# Power_Supplies.net
KiCad netlist of a schematic drawn in Altium Designer
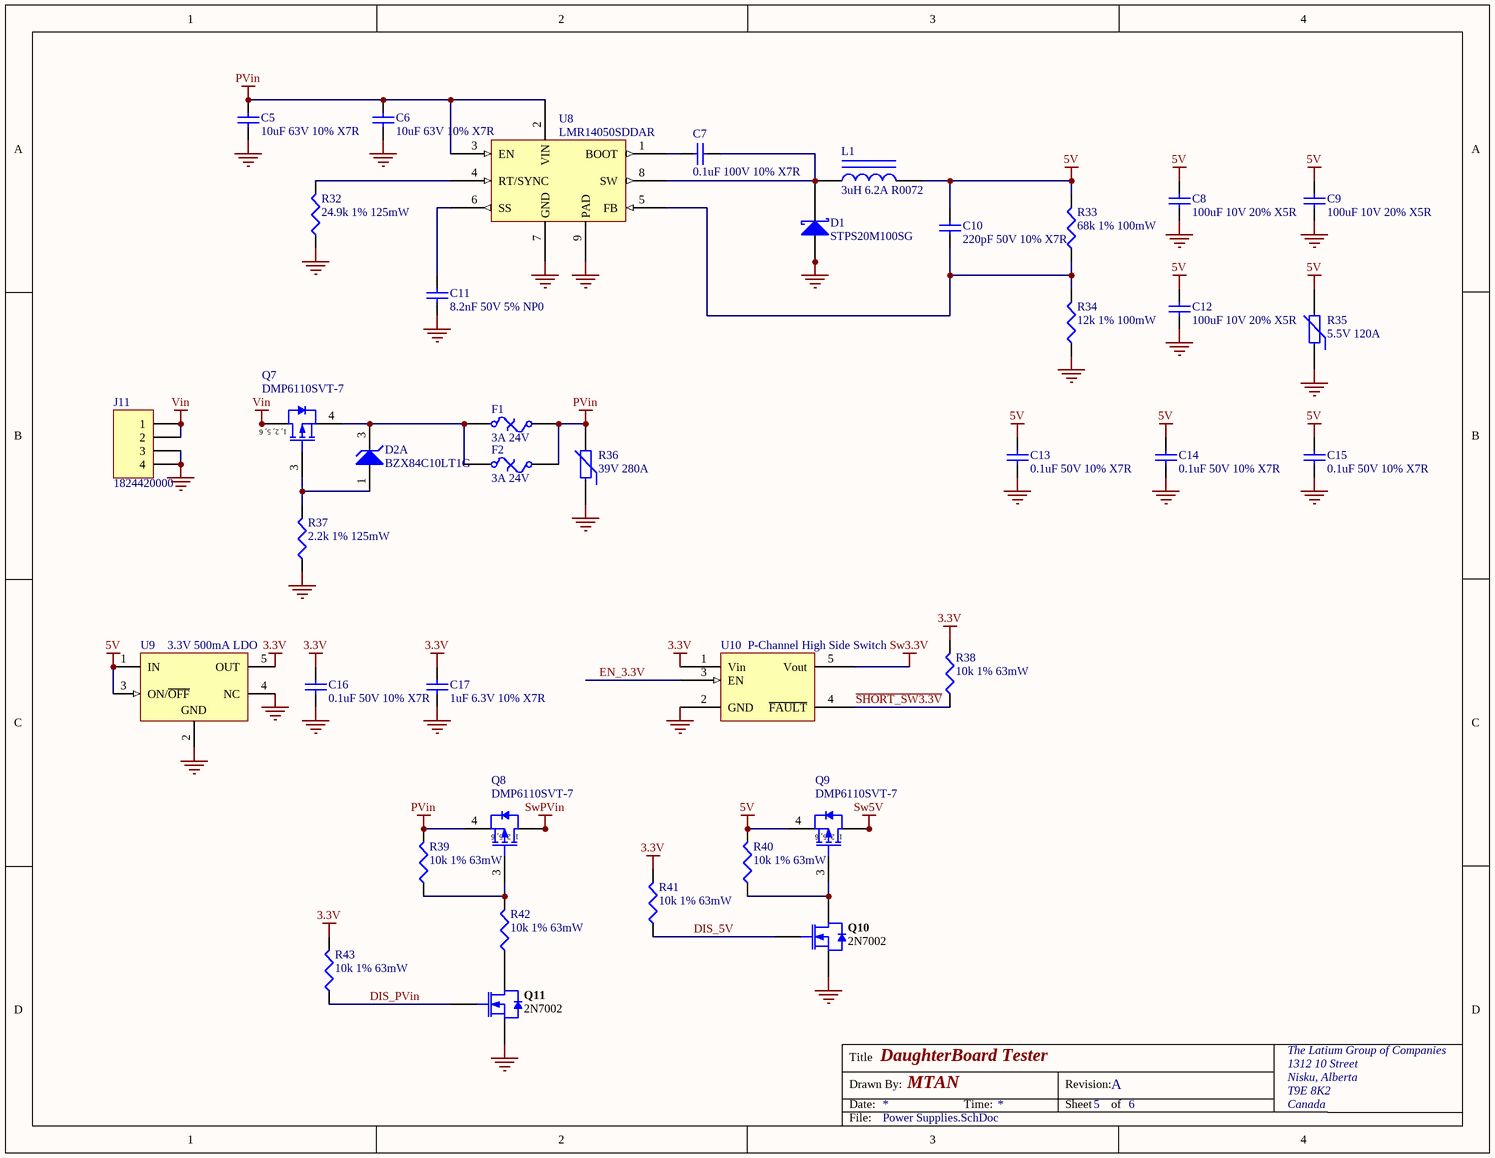
[diagram p0: Power Supplies.SchDoc]

(export (version "E")
  (design (tool "Eeschema 10.0.6"))
  (components
    (comp (ref "C5")
      (value "10uF 63V 10% X7R")
      (footprint "C1210_L")
      (description "Capacitor")
      (libsource (lib "Miscellaneous Devices") (part "Cap"))
    )
    (comp (ref "C6")
      (value "10uF 63V 10% X7R")
      (footprint "C1210_L")
      (description "Capacitor")
      (libsource (lib "Miscellaneous Devices") (part "Cap"))
    )
    (comp (ref "C7")
      (value "0.1uF 100V 10% X7R")
      (footprint "C0805")
      (description "Capacitor")
      (libsource (lib "Miscellaneous Devices") (part "Cap"))
    )
    (comp (ref "C8")
      (value "100uF 10V 20% X5R")
      (footprint "C1210_L")
      (description "Capacitor")
      (libsource (lib "Miscellaneous Devices") (part "Cap"))
    )
    (comp (ref "C9")
      (value "100uF 10V 20% X5R")
      (footprint "C1210_L")
      (description "Capacitor")
      (libsource (lib "Miscellaneous Devices") (part "Cap"))
    )
    (comp (ref "C10")
      (value "220pF 50V 10% X7R")
      (footprint "1608[0603]")
      (description "Capacitor")
      (libsource (lib "Miscellaneous Devices") (part "Cap"))
    )
    (comp (ref "C11")
      (value "8.2nF 50V 5% NP0")
      (footprint "1608[0603]")
      (description "Capacitor")
      (libsource (lib "Miscellaneous Devices") (part "Cap"))
    )
    (comp (ref "C12")
      (value "100uF 10V 20% X5R")
      (footprint "C1210_L")
      (description "Capacitor")
      (libsource (lib "Miscellaneous Devices") (part "Cap"))
    )
    (comp (ref "C13")
      (value "0.1uF 50V 10% X7R")
      (footprint "CAPC1005L")
      (description "Capacitor")
      (libsource (lib "Miscellaneous Devices") (part "Cap"))
    )
    (comp (ref "C14")
      (value "0.1uF 50V 10% X7R")
      (footprint "CAPC1005L")
      (description "Capacitor")
      (libsource (lib "Miscellaneous Devices") (part "Cap"))
    )
    (comp (ref "C15")
      (value "0.1uF 50V 10% X7R")
      (footprint "CAPC1005L")
      (description "Capacitor")
      (libsource (lib "Miscellaneous Devices") (part "Cap"))
    )
    (comp (ref "C16")
      (value "0.1uF 50V 10% X7R")
      (footprint "CAPC1005L")
      (description "Capacitor")
      (libsource (lib "Miscellaneous Devices") (part "Cap"))
    )
    (comp (ref "C17")
      (value "1uF 6.3V 10% X7R")
      (footprint "CAPC1005L")
      (description "Capacitor")
      (libsource (lib "Miscellaneous Devices") (part "Cap"))
    )
    (comp (ref "D1")
      (value "STPS20M100SG")
      (footprint "ONSC-D2PAK-3-418AJ_A_V")
      (description "DIODE SCHOTTKY 100V 20A D2PAK")
      (fields (field (name "MANUFACTURER") "STMicroelectronics"))
      (libsource (lib "Infineon Discrete Diode") (part "BAS70"))
    )
    (comp (ref "D2")
      (value "BZX84C10LT1G")
      (footprint "SOT23-3_L")
      (description "DIODE ZENER 10V 225MW SOT23-3")
      (fields (field (name "MANUFACTURER") "On Semiconductor"))
      (libsource (lib "ON Semi Zener Diodes") (part "BZX84C10LT1G"))
    )
    (comp (ref "F1")
      (value "3A 24V")
      (footprint "2920")
      (description "Thermal Fuse")
      (fields
        (field (name "MANUFACTURER PART NUMBER") "SMDC300F/24-2")
        (field (name "MANUFACTURER") "Littelfuse Inc")
      )
      (libsource (lib "Miscellaneous Devices") (part "Fuse Thermal"))
    )
    (comp (ref "F2")
      (value "3A 24V")
      (footprint "2920")
      (description "Thermal Fuse")
      (fields
        (field (name "MANUFACTURER PART NUMBER") "SMDC300F/24-2")
        (field (name "MANUFACTURER") "Littelfuse Inc")
      )
      (libsource (lib "Miscellaneous Devices") (part "Fuse Thermal"))
    )
    (comp (ref "J11")
      (value "1824420000")
      (footprint "1824420000")
      (description "TERM BLK 2POS SIDE ENT 3.5MM PCB")
      (fields (field (name "MANUFACTURER") "Weidmuller"))
      (libsource (lib "Miscellaneous Connectors") (part "Header 4H"))
    )
    (comp (ref "L1")
      (value "3uH 6.2A R0072")
      (footprint "SRU1048")
      (description "FIXED IND 3UH 6.2A 7.2 MOHM SMD")
      (fields
        (field (name "MANUFACTURER PART NUMBER") "SRU1048-3R0Y")
        (field (name "MANUFACTURER") "Bourns Inc")
      )
      (libsource (lib "Miscellaneous Devices") (part "Inductor Iron"))
    )
    (comp (ref "Q7")
      (value "DMP6110SVT-7")
      (footprint "SOT23-6_L")
      (description "MOSFET P-CH 60V TSOT26")
      (fields (field (name "MANUFACTURER") "Diodes Incorporated"))
      (libsource (lib "ON Semi MOSFETs") (part "NTGS3136PT1G"))
    )
    (comp (ref "Q8")
      (value "DMP6110SVT-7")
      (footprint "SOT23-6_L")
      (description "MOSFET P-CH 60V TSOT26")
      (fields (field (name "MANUFACTURER") "Diodes Incorporated"))
      (libsource (lib "ON Semi MOSFETs") (part "NTGS3136PT1G"))
    )
    (comp (ref "Q9")
      (value "DMP6110SVT-7")
      (footprint "SOT23-6_L")
      (description "MOSFET P-CH 60V TSOT26")
      (fields (field (name "MANUFACTURER") "Diodes Incorporated"))
      (libsource (lib "ON Semi MOSFETs") (part "NTGS3136PT1G"))
    )
    (comp (ref "Q10")
      (value "2N7002")
      (footprint "INF-PG-SOT23_L")
      (description "MOSFET N-CH 60V 115MA SOT-23")
      (fields (field (name "MANUFACTURER") "ON Semiconductor"))
      (libsource (lib "Infineon Power MOSFET") (part "2N7002"))
    )
    (comp (ref "Q11")
      (value "2N7002")
      (footprint "INF-PG-SOT23_L")
      (description "MOSFET N-CH 60V 115MA SOT-23")
      (fields (field (name "MANUFACTURER") "ON Semiconductor"))
      (libsource (lib "Infineon Power MOSFET") (part "2N7002"))
    )
    (comp (ref "R32")
      (value "24.9k 1% 125mW")
      (footprint "6-0805_L")
      (description "Resistor")
      (libsource (lib "Miscellaneous Devices") (part "Res3"))
    )
    (comp (ref "R33")
      (value "68k 1% 100mW")
      (footprint "J1-0603")
      (description "Resistor")
      (libsource (lib "Miscellaneous Devices") (part "Res3"))
    )
    (comp (ref "R34")
      (value "12k 1% 100mW")
      (footprint "J1-0603")
      (description "Resistor")
      (libsource (lib "Miscellaneous Devices") (part "Res3"))
    )
    (comp (ref "R35")
      (value "5.5V 120A")
      (footprint "6-0805_L")
      (description "VARISTOR 8.2V 120A 0805")
      (fields
        (field (name "MANUFACTURER") "Littelfuse Inc")
        (field (name "MANUFACTURER PART NUMBER") "V5.5MLA0805H")
      )
      (libsource (lib "Miscellaneous Devices") (part "Res Varistor"))
    )
    (comp (ref "R36")
      (value "39V 280A")
      (footprint "RESC3225L")
      (description "VARISTOR 39V 280A 1210")
      (fields
        (field (name "MANUFACTURER") "Littelfuse Inc")
        (field (name "MANUFACTURER PART NUMBER") "V30MLA1210NH")
      )
      (libsource (lib "Miscellaneous Devices") (part "Res Varistor"))
    )
    (comp (ref "R37")
      (value "2.2k 1% 125mW")
      (footprint "6-0805_L")
      (description "Resistor")
      (libsource (lib "Miscellaneous Devices") (part "Res3"))
    )
    (comp (ref "R38")
      (value "10k 1% 63mW")
      (footprint "RESC1005L")
      (description "Resistor")
      (libsource (lib "Miscellaneous Devices") (part "Res3"))
    )
    (comp (ref "R39")
      (value "10k 1% 63mW")
      (footprint "RESC1005L")
      (description "Resistor")
      (libsource (lib "Miscellaneous Devices") (part "Res3"))
    )
    (comp (ref "R40")
      (value "10k 1% 63mW")
      (footprint "RESC1005L")
      (description "Resistor")
      (libsource (lib "Miscellaneous Devices") (part "Res3"))
    )
    (comp (ref "R41")
      (value "10k 1% 63mW")
      (footprint "RESC1005L")
      (description "Resistor")
      (libsource (lib "Miscellaneous Devices") (part "Res3"))
    )
    (comp (ref "R42")
      (value "10k 1% 63mW")
      (footprint "RESC1005L")
      (description "Resistor")
      (libsource (lib "Miscellaneous Devices") (part "Res3"))
    )
    (comp (ref "R43")
      (value "10k 1% 63mW")
      (footprint "RESC1005L")
      (description "Resistor")
      (libsource (lib "Miscellaneous Devices") (part "Res3"))
    )
    (comp (ref "U8")
      (value "LMR14050SDDAR")
      (footprint "MRA08A_L")
      (description "IC REG BUCK ADJUSTABLE 5A 8SOPWR")
      (fields (field (name "MANUFACTURER") "Texas Instruments"))
      (libsource (lib "Latium Component Library") (part "LMR14050"))
    )
    (comp (ref "U9")
      (value "3.3V 500mA LDO")
      (footprint "MF05A_L")
      (description "IC REG LINEAR 3.3V 500MA SOT23-5")
      (fields
        (field (name "MANUFACTURER") "Texas Instruments")
        (field (name "MANUFACTURER PART NUMBER") "TLV75533PDBVR")
      )
      (libsource (lib "LDO") (part "LP2985AIM5X-6.1/NOPB"))
    )
    (comp (ref "U10")
      (value "P-Channel High Side Switch")
      (footprint "SOT23-5_L")
      (description "IC PWR SWITCH P-CHAN 1:1 SOT23-5")
      (fields
        (field (name "MANUFACTURER") "Microchip Technology")
        (field (name "MANUFACTURER PART NUMBER") "MIC2005A-1YM5-TR")
      )
      (libsource (lib "Latium Component Library") (part "MIC2005A-1YM5-TR"))
    )
  )
  (nets
    (net (code "1") (name "/DIS_5V") (class "Default")
      (node (ref "Q10") (pin "1") (pinfunction "GATE_1") (pintype "passive"))
      (node (ref "R41") (pin "1") (pinfunction "1_1") (pintype "passive"))
    )
    (net (code "2") (name "/DIS_PVin") (class "Default")
      (node (ref "Q11") (pin "1") (pinfunction "GATE_1") (pintype "passive"))
      (node (ref "R43") (pin "1") (pinfunction "1_1") (pintype "passive"))
    )
    (net (code "3") (name "/EN_3.3V") (class "Default")
      (node (ref "U10") (pin "3") (pinfunction "EN_3") (pintype "input"))
    )
    (net (code "4") (name "/~{SHORT_SW3.3V}") (class "Default")
      (node (ref "R38") (pin "1") (pinfunction "1_1") (pintype "passive"))
      (node (ref "U10") (pin "4") (pinfunction "~{FAULT}_4") (pintype "open_collector"))
    )
    (net (code "5") (name "3.3V") (class "Default")
      (node (ref "C16") (pin "1") (pinfunction "1_1") (pintype "passive"))
      (node (ref "C17") (pin "1") (pinfunction "1_1") (pintype "passive"))
      (node (ref "R38") (pin "2") (pinfunction "2_2") (pintype "passive"))
      (node (ref "R41") (pin "2") (pinfunction "2_2") (pintype "passive"))
      (node (ref "R43") (pin "2") (pinfunction "2_2") (pintype "passive"))
      (node (ref "U10") (pin "1") (pinfunction "Vin_1") (pintype "power_in"))
      (node (ref "U9") (pin "5") (pinfunction "OUT_5") (pintype "power_in"))
    )
    (net (code "6") (name "5V") (class "Default")
      (node (ref "C10") (pin "2") (pinfunction "2_2") (pintype "passive"))
      (node (ref "C12") (pin "2") (pinfunction "2_2") (pintype "passive"))
      (node (ref "C13") (pin "1") (pinfunction "1_1") (pintype "passive"))
      (node (ref "C14") (pin "1") (pinfunction "1_1") (pintype "passive"))
      (node (ref "C15") (pin "1") (pinfunction "1_1") (pintype "passive"))
      (node (ref "C8") (pin "2") (pinfunction "2_2") (pintype "passive"))
      (node (ref "C9") (pin "2") (pinfunction "2_2") (pintype "passive"))
      (node (ref "L1") (pin "2") (pinfunction "2_2") (pintype "passive"))
      (node (ref "Q9") (pin "4") (pinfunction "S_4") (pintype "passive"))
      (node (ref "R33") (pin "2") (pinfunction "2_2") (pintype "passive"))
      (node (ref "R35") (pin "2") (pinfunction "2_2") (pintype "passive"))
      (node (ref "R40") (pin "2") (pinfunction "2_2") (pintype "passive"))
      (node (ref "U9") (pin "1") (pinfunction "IN_1") (pintype "power_in"))
      (node (ref "U9") (pin "3") (pinfunction "ON/~{OFF}_3") (pintype "input"))
    )
    (net (code "7") (name "GND") (class "Default")
      (node (ref "C11") (pin "1") (pinfunction "1_1") (pintype "passive"))
      (node (ref "C12") (pin "1") (pinfunction "1_1") (pintype "passive"))
      (node (ref "C13") (pin "2") (pinfunction "2_2") (pintype "passive"))
      (node (ref "C14") (pin "2") (pinfunction "2_2") (pintype "passive"))
      (node (ref "C15") (pin "2") (pinfunction "2_2") (pintype "passive"))
      (node (ref "C16") (pin "2") (pinfunction "2_2") (pintype "passive"))
      (node (ref "C17") (pin "2") (pinfunction "2_2") (pintype "passive"))
      (node (ref "C5") (pin "1") (pinfunction "1_1") (pintype "passive"))
      (node (ref "C6") (pin "1") (pinfunction "1_1") (pintype "passive"))
      (node (ref "C8") (pin "1") (pinfunction "1_1") (pintype "passive"))
      (node (ref "C9") (pin "1") (pinfunction "1_1") (pintype "passive"))
      (node (ref "D1") (pin "1") (pinfunction "A_1") (pintype "passive"))
      (node (ref "D1") (pin "3") (pinfunction "A_3") (pintype "passive"))
      (node (ref "J11") (pin "3") (pinfunction "3_3") (pintype "passive"))
      (node (ref "J11") (pin "4") (pinfunction "4_4") (pintype "passive"))
      (node (ref "Q10") (pin "2") (pinfunction "SOURCE_2") (pintype "passive"))
      (node (ref "Q11") (pin "2") (pinfunction "SOURCE_2") (pintype "passive"))
      (node (ref "R32") (pin "1") (pinfunction "1_1") (pintype "passive"))
      (node (ref "R34") (pin "1") (pinfunction "1_1") (pintype "passive"))
      (node (ref "R35") (pin "1") (pinfunction "1_1") (pintype "passive"))
      (node (ref "R36") (pin "1") (pinfunction "1_1") (pintype "passive"))
      (node (ref "R37") (pin "1") (pinfunction "1_1") (pintype "passive"))
      (node (ref "U10") (pin "2") (pinfunction "GND_2") (pintype "power_in"))
      (node (ref "U8") (pin "7") (pinfunction "GND_7") (pintype "power_in"))
      (node (ref "U8") (pin "9") (pinfunction "PAD_9") (pintype "power_in"))
      (node (ref "U9") (pin "2") (pinfunction "GND_2") (pintype "power_in"))
      (node (ref "U9") (pin "4") (pinfunction "NC_4") (pintype "passive"))
    )
    (net (code "8") (name "Net-(D1-K)") (class "Default")
      (node (ref "C7") (pin "1") (pinfunction "1_1") (pintype "passive"))
      (node (ref "D1") (pin "4") (pinfunction "K_4") (pintype "passive"))
      (node (ref "L1") (pin "1") (pinfunction "1_1") (pintype "passive"))
      (node (ref "U8") (pin "8") (pinfunction "SW_8") (pintype "output"))
    )
    (net (code "9") (name "Net-(D2A-A)") (class "Default")
      (node (ref "D2") (pin "1") (pinfunction "A_1") (pintype "passive"))
      (node (ref "Q7") (pin "3") (pinfunction "G_3") (pintype "passive"))
      (node (ref "R37") (pin "2") (pinfunction "2_2") (pintype "passive"))
    )
    (net (code "10") (name "Net-(D2A-K)") (class "Default")
      (node (ref "D2") (pin "3") (pinfunction "K_3") (pintype "passive"))
      (node (ref "F1") (pin "1") (pinfunction "1_1") (pintype "passive"))
      (node (ref "F2") (pin "1") (pinfunction "1_1") (pintype "passive"))
      (node (ref "Q7") (pin "4") (pinfunction "S_4") (pintype "passive"))
    )
    (net (code "11") (name "Net-(Q8-G)") (class "Default")
      (node (ref "Q8") (pin "3") (pinfunction "G_3") (pintype "passive"))
      (node (ref "R39") (pin "1") (pinfunction "1_1") (pintype "passive"))
      (node (ref "R42") (pin "2") (pinfunction "2_2") (pintype "passive"))
    )
    (net (code "12") (name "Net-(Q10-DRAIN)") (class "Default")
      (node (ref "Q10") (pin "3") (pinfunction "DRAIN_3") (pintype "passive"))
      (node (ref "Q9") (pin "3") (pinfunction "G_3") (pintype "passive"))
      (node (ref "R40") (pin "1") (pinfunction "1_1") (pintype "passive"))
    )
    (net (code "13") (name "Net-(Q11-DRAIN)") (class "Default")
      (node (ref "Q11") (pin "3") (pinfunction "DRAIN_3") (pintype "passive"))
      (node (ref "R42") (pin "1") (pinfunction "1_1") (pintype "passive"))
    )
    (net (code "14") (name "Net-(U8-BOOT)") (class "Default")
      (node (ref "C7") (pin "2") (pinfunction "2_2") (pintype "passive"))
      (node (ref "U8") (pin "1") (pinfunction "BOOT_1") (pintype "output"))
    )
    (net (code "15") (name "Net-(U8-FB)") (class "Default")
      (node (ref "C10") (pin "1") (pinfunction "1_1") (pintype "passive"))
      (node (ref "R33") (pin "1") (pinfunction "1_1") (pintype "passive"))
      (node (ref "R34") (pin "2") (pinfunction "2_2") (pintype "passive"))
      (node (ref "U8") (pin "5") (pinfunction "FB_5") (pintype "input"))
    )
    (net (code "16") (name "Net-(U8-RT{slash}SYNC)") (class "Default")
      (node (ref "R32") (pin "2") (pinfunction "2_2") (pintype "passive"))
      (node (ref "U8") (pin "4") (pinfunction "RT/SYNC_4") (pintype "input"))
    )
    (net (code "17") (name "Net-(U8-SS)") (class "Default")
      (node (ref "C11") (pin "2") (pinfunction "2_2") (pintype "passive"))
      (node (ref "U8") (pin "6") (pinfunction "SS_6") (pintype "output"))
    )
    (net (code "18") (name "PVin") (class "Default")
      (node (ref "C5") (pin "2") (pinfunction "2_2") (pintype "passive"))
      (node (ref "C6") (pin "2") (pinfunction "2_2") (pintype "passive"))
      (node (ref "F1") (pin "2") (pinfunction "2_2") (pintype "passive"))
      (node (ref "F2") (pin "2") (pinfunction "2_2") (pintype "passive"))
      (node (ref "Q8") (pin "4") (pinfunction "S_4") (pintype "passive"))
      (node (ref "R36") (pin "2") (pinfunction "2_2") (pintype "passive"))
      (node (ref "R39") (pin "2") (pinfunction "2_2") (pintype "passive"))
      (node (ref "U8") (pin "2") (pinfunction "VIN_2") (pintype "power_in"))
      (node (ref "U8") (pin "3") (pinfunction "EN_3") (pintype "input"))
    )
    (net (code "19") (name "Sw3.3V") (class "Default")
      (node (ref "U10") (pin "5") (pinfunction "Vout_5") (pintype "power_in"))
    )
    (net (code "20") (name "Sw5V") (class "Default")
      (node (ref "Q9") (pin "1") (pinfunction "D_1") (pintype "passive"))
      (node (ref "Q9") (pin "2") (pinfunction "D_2") (pintype "passive"))
      (node (ref "Q9") (pin "5") (pinfunction "D_5") (pintype "passive"))
      (node (ref "Q9") (pin "6") (pinfunction "D_6") (pintype "passive"))
    )
    (net (code "21") (name "SwPVin") (class "Default")
      (node (ref "Q8") (pin "1") (pinfunction "D_1") (pintype "passive"))
      (node (ref "Q8") (pin "2") (pinfunction "D_2") (pintype "passive"))
      (node (ref "Q8") (pin "5") (pinfunction "D_5") (pintype "passive"))
      (node (ref "Q8") (pin "6") (pinfunction "D_6") (pintype "passive"))
    )
    (net (code "22") (name "Vin") (class "Default")
      (node (ref "J11") (pin "1") (pinfunction "1_1") (pintype "passive"))
      (node (ref "J11") (pin "2") (pinfunction "2_2") (pintype "passive"))
      (node (ref "Q7") (pin "1") (pinfunction "D_1") (pintype "passive"))
      (node (ref "Q7") (pin "2") (pinfunction "D_2") (pintype "passive"))
      (node (ref "Q7") (pin "5") (pinfunction "D_5") (pintype "passive"))
      (node (ref "Q7") (pin "6") (pinfunction "D_6") (pintype "passive"))
    )
  )
)
